# Filter_Capacitors_-_IoT_UART.net
KiCad netlist of a schematic drawn in Altium Designer
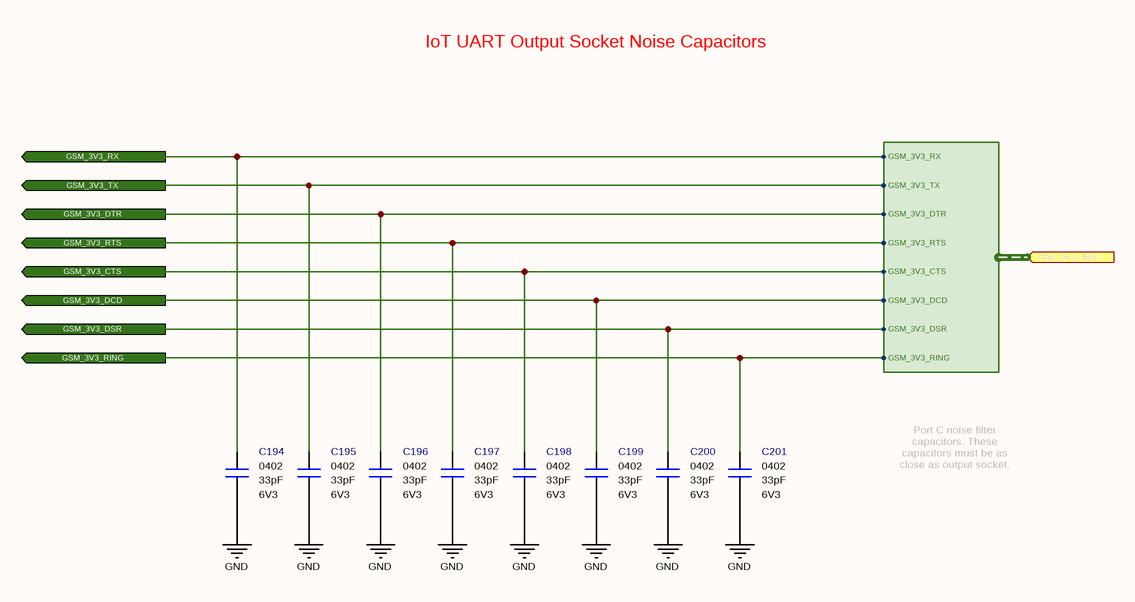
[diagram p0: Filter Capacitors - IoT UART.SchDoc]

(export (version "E")
  (design (tool "Eeschema 10.0.6"))
  (components
    (comp (ref "C194")
      (value "33pF")
      (footprint "CAPACITOR_0402")
      (description "Capacitor - 33pF [0402] (Ceramic)")
      (fields
        (field (name "TOLERANCE") "10%")
        (field (name "CASE") "0402")
        (field (name "VOLTAGE") "6V3")
        (field (name "MANUFACTURER PART NUMBER") "C0402C330J9RACAUTO")
      )
      (libsource (lib "Ovoo_Library") (part "Capacitor - 33pF [0402-6V3]"))
    )
    (comp (ref "C195")
      (value "33pF")
      (footprint "CAPACITOR_0402")
      (description "Capacitor - 33pF [0402] (Ceramic)")
      (fields
        (field (name "TOLERANCE") "10%")
        (field (name "CASE") "0402")
        (field (name "VOLTAGE") "6V3")
        (field (name "MANUFACTURER PART NUMBER") "C0402C330J9RACAUTO")
      )
      (libsource (lib "Ovoo_Library") (part "Capacitor - 33pF [0402-6V3]"))
    )
    (comp (ref "C196")
      (value "33pF")
      (footprint "CAPACITOR_0402")
      (description "Capacitor - 33pF [0402] (Ceramic)")
      (fields
        (field (name "TOLERANCE") "10%")
        (field (name "CASE") "0402")
        (field (name "VOLTAGE") "6V3")
        (field (name "MANUFACTURER PART NUMBER") "C0402C330J9RACAUTO")
      )
      (libsource (lib "Ovoo_Library") (part "Capacitor - 33pF [0402-6V3]"))
    )
    (comp (ref "C197")
      (value "33pF")
      (footprint "CAPACITOR_0402")
      (description "Capacitor - 33pF [0402] (Ceramic)")
      (fields
        (field (name "TOLERANCE") "10%")
        (field (name "CASE") "0402")
        (field (name "VOLTAGE") "6V3")
        (field (name "MANUFACTURER PART NUMBER") "C0402C330J9RACAUTO")
      )
      (libsource (lib "Ovoo_Library") (part "Capacitor - 33pF [0402-6V3]"))
    )
    (comp (ref "C198")
      (value "33pF")
      (footprint "CAPACITOR_0402")
      (description "Capacitor - 33pF [0402] (Ceramic)")
      (fields
        (field (name "TOLERANCE") "10%")
        (field (name "CASE") "0402")
        (field (name "VOLTAGE") "6V3")
        (field (name "MANUFACTURER PART NUMBER") "C0402C330J9RACAUTO")
      )
      (libsource (lib "Ovoo_Library") (part "Capacitor - 33pF [0402-6V3]"))
    )
    (comp (ref "C199")
      (value "33pF")
      (footprint "CAPACITOR_0402")
      (description "Capacitor - 33pF [0402] (Ceramic)")
      (fields
        (field (name "TOLERANCE") "10%")
        (field (name "CASE") "0402")
        (field (name "VOLTAGE") "6V3")
        (field (name "MANUFACTURER PART NUMBER") "C0402C330J9RACAUTO")
      )
      (libsource (lib "Ovoo_Library") (part "Capacitor - 33pF [0402-6V3]"))
    )
    (comp (ref "C200")
      (value "33pF")
      (footprint "CAPACITOR_0402")
      (description "Capacitor - 33pF [0402] (Ceramic)")
      (fields
        (field (name "TOLERANCE") "10%")
        (field (name "CASE") "0402")
        (field (name "VOLTAGE") "6V3")
        (field (name "MANUFACTURER PART NUMBER") "C0402C330J9RACAUTO")
      )
      (libsource (lib "Ovoo_Library") (part "Capacitor - 33pF [0402-6V3]"))
    )
    (comp (ref "C201")
      (value "33pF")
      (footprint "CAPACITOR_0402")
      (description "Capacitor - 33pF [0402] (Ceramic)")
      (fields
        (field (name "TOLERANCE") "10%")
        (field (name "CASE") "0402")
        (field (name "VOLTAGE") "6V3")
        (field (name "MANUFACTURER PART NUMBER") "C0402C330J9RACAUTO")
      )
      (libsource (lib "Ovoo_Library") (part "Capacitor - 33pF [0402-6V3]"))
    )
  )
  (nets
    (net (code "2") (name "/GSM_3V3_CTS") (class "Default")
      (node (ref "C198") (pin "2") (pinfunction "2_2") (pintype "passive"))
    )
    (net (code "3") (name "/GSM_3V3_DCD") (class "Default")
      (node (ref "C199") (pin "2") (pinfunction "2_2") (pintype "passive"))
    )
    (net (code "4") (name "/GSM_3V3_DSR") (class "Default")
      (node (ref "C200") (pin "2") (pinfunction "2_2") (pintype "passive"))
    )
    (net (code "5") (name "/GSM_3V3_DTR") (class "Default")
      (node (ref "C196") (pin "2") (pinfunction "2_2") (pintype "passive"))
    )
    (net (code "6") (name "/GSM_3V3_RING") (class "Default")
      (node (ref "C201") (pin "2") (pinfunction "2_2") (pintype "passive"))
    )
    (net (code "7") (name "/GSM_3V3_RTS") (class "Default")
      (node (ref "C197") (pin "2") (pinfunction "2_2") (pintype "passive"))
    )
    (net (code "8") (name "/GSM_3V3_RX") (class "Default")
      (node (ref "C194") (pin "2") (pinfunction "2_2") (pintype "passive"))
    )
    (net (code "9") (name "/GSM_3V3_TX") (class "Default")
      (node (ref "C195") (pin "2") (pinfunction "2_2") (pintype "passive"))
    )
    (net (code "11") (name "GND") (class "Default")
      (node (ref "C194") (pin "1") (pinfunction "1_1") (pintype "passive"))
      (node (ref "C195") (pin "1") (pinfunction "1_1") (pintype "passive"))
      (node (ref "C196") (pin "1") (pinfunction "1_1") (pintype "passive"))
      (node (ref "C197") (pin "1") (pinfunction "1_1") (pintype "passive"))
      (node (ref "C198") (pin "1") (pinfunction "1_1") (pintype "passive"))
      (node (ref "C199") (pin "1") (pinfunction "1_1") (pintype "passive"))
      (node (ref "C200") (pin "1") (pinfunction "1_1") (pintype "passive"))
      (node (ref "C201") (pin "1") (pinfunction "1_1") (pintype "passive"))
    )
  )
)
